# Sampling.net
KiCad netlist of a schematic drawn in Altium Designer
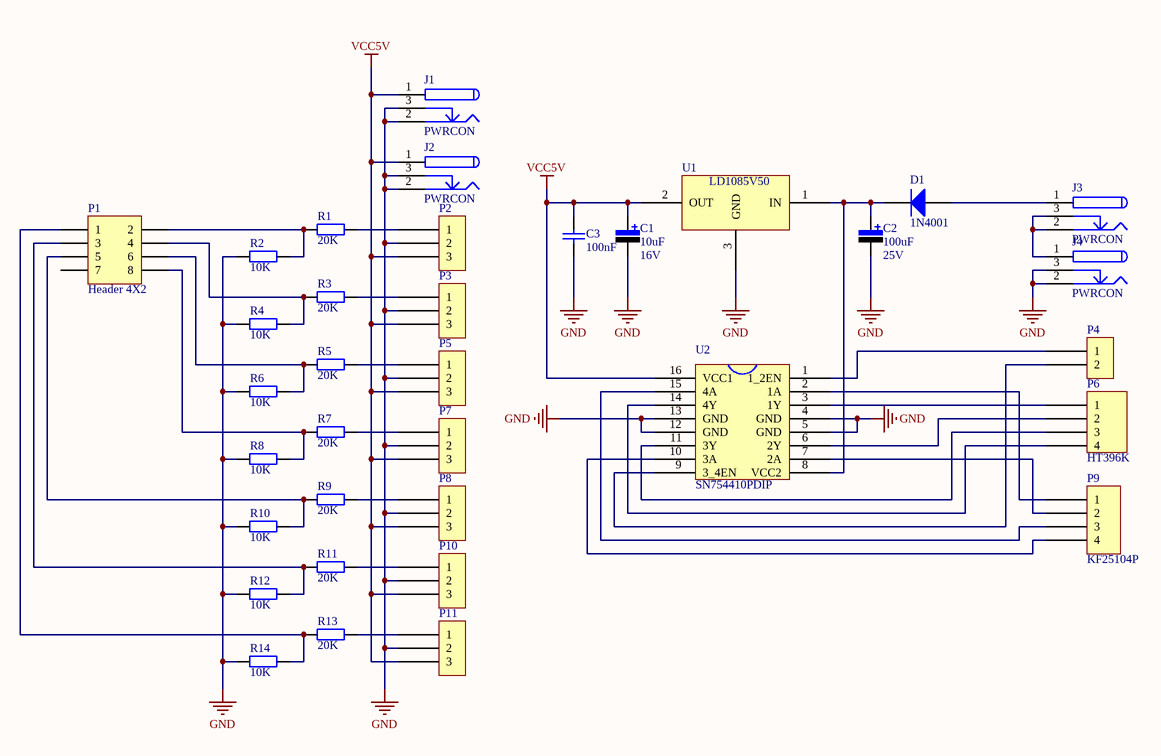
[diagram p0: Sampling.SchDoc]

(export (version "E")
  (design (tool "Eeschema 10.0.6"))
  (components
    (comp (ref "C1")
      (value "10uF")
      (footprint "C-RB-S4")
      (description "极性电解电容")
      (fields
        (field (name "VOL") "16V")
        (field (name "Comment") "Cap Pol")
        (field (name "PUBLISHER") "Altium Limited")
      )
      (libsource (lib "fszhang") (part "Cap Pol"))
    )
    (comp (ref "C2")
      (value "100uF")
      (footprint "C-RB-S6")
      (description "极性电解电容")
      (fields
        (field (name "VOL") "25V")
        (field (name "Comment") "Cap Pol")
        (field (name "PUBLISHER") "Altium Limited")
      )
      (libsource (lib "fszhang") (part "Cap Pol"))
    )
    (comp (ref "C3")
      (value "100nF")
      (footprint "C-RAD-0805")
      (description "无极性电容")
      (fields (field (name "Comment") "Cap") (field (name "PUBLISHER") "Altium Limited"))
      (libsource (lib "fszhang") (part "Cap"))
    )
    (comp (ref "D1")
      (value "Diode")
      (footprint "DIODE-SMA")
      (description "二极管")
      (fields (field (name "TYPE") "1N4001") (field (name "PUBLISHER") "Altium Limited"))
      (libsource (lib "fszhang") (part "Diode"))
    )
    (comp (ref "J1")
      (value "PWRCON")
      (footprint "DC-005")
      (description "直流电源端子")
      (fields (field (name "PUBLISHER") "Altium Limited"))
      (libsource (lib "fszhang") (part "PWRCON"))
    )
    (comp (ref "J2")
      (value "PWRCON")
      (footprint "DC-005")
      (description "直流电源端子")
      (fields (field (name "PUBLISHER") "Altium Limited"))
      (libsource (lib "fszhang") (part "PWRCON"))
    )
    (comp (ref "J3")
      (value "PWRCON")
      (footprint "DC-005")
      (description "直流电源端子")
      (fields (field (name "PUBLISHER") "Altium Limited"))
      (libsource (lib "fszhang") (part "PWRCON"))
    )
    (comp (ref "J4")
      (value "PWRCON")
      (footprint "DC-005")
      (description "直流电源端子")
      (fields (field (name "PUBLISHER") "Altium Limited"))
      (libsource (lib "fszhang") (part "PWRCON"))
    )
    (comp (ref "P1")
      (value "Header 4X2")
      (footprint "HDR2X4")
      (description "Header, 4-Pin, Dual row")
      (fields (field (name "PUBLISHER") "Altium Limited"))
      (libsource (lib "Miscellaneous Connectors") (part "Header 4X2"))
    )
    (comp (ref "P2") (value "KF25103P") (footprint "KF25103P") (libsource (lib "fszhang") (part "KF25103P")))
    (comp (ref "P3") (value "KF25103P") (footprint "KF25103P") (libsource (lib "fszhang") (part "KF25103P")))
    (comp (ref "P4") (value "KF25102P") (footprint "KF25102P") (libsource (lib "fszhang") (part "KF25102P")))
    (comp (ref "P5") (value "KF25103P") (footprint "KF25103P") (libsource (lib "fszhang") (part "KF25103P")))
    (comp (ref "P6") (value "HT396K") (footprint "HT396K") (libsource (lib "fszhang") (part "HT396K")))
    (comp (ref "P7") (value "KF25103P") (footprint "KF25103P") (libsource (lib "fszhang") (part "KF25103P")))
    (comp (ref "P8") (value "KF25103P") (footprint "KF25103P") (libsource (lib "fszhang") (part "KF25103P")))
    (comp (ref "P9") (value "KF25104P") (footprint "KF25104P") (libsource (lib "fszhang") (part "KF25104P")))
    (comp (ref "P10") (value "KF25103P") (footprint "KF25103P") (libsource (lib "fszhang") (part "KF25103P")))
    (comp (ref "P11") (value "KF25103P") (footprint "KF25103P") (libsource (lib "fszhang") (part "KF25103P")))
    (comp (ref "R1")
      (value "20K")
      (footprint "0805-1")
      (description "贴片电阻")
      (fields (field (name "Comment") "Res1") (field (name "PUBLISHER") "Altium Limited"))
      (libsource (lib "fszhang") (part "Res1"))
    )
    (comp (ref "R2")
      (value "10K")
      (footprint "0805-1")
      (description "贴片电阻")
      (fields (field (name "Comment") "Res1") (field (name "PUBLISHER") "Altium Limited"))
      (libsource (lib "fszhang") (part "Res1"))
    )
    (comp (ref "R3")
      (value "20K")
      (footprint "0805-1")
      (description "贴片电阻")
      (fields (field (name "Comment") "Res1") (field (name "PUBLISHER") "Altium Limited"))
      (libsource (lib "fszhang") (part "Res1"))
    )
    (comp (ref "R4")
      (value "10K")
      (footprint "0805-1")
      (description "贴片电阻")
      (fields (field (name "Comment") "Res1") (field (name "PUBLISHER") "Altium Limited"))
      (libsource (lib "fszhang") (part "Res1"))
    )
    (comp (ref "R5")
      (value "20K")
      (footprint "0805-1")
      (description "贴片电阻")
      (fields (field (name "Comment") "Res1") (field (name "PUBLISHER") "Altium Limited"))
      (libsource (lib "fszhang") (part "Res1"))
    )
    (comp (ref "R6")
      (value "10K")
      (footprint "0805-1")
      (description "贴片电阻")
      (fields (field (name "Comment") "Res1") (field (name "PUBLISHER") "Altium Limited"))
      (libsource (lib "fszhang") (part "Res1"))
    )
    (comp (ref "R7")
      (value "20K")
      (footprint "0805-1")
      (description "贴片电阻")
      (fields (field (name "Comment") "Res1") (field (name "PUBLISHER") "Altium Limited"))
      (libsource (lib "fszhang") (part "Res1"))
    )
    (comp (ref "R8")
      (value "10K")
      (footprint "0805-1")
      (description "贴片电阻")
      (fields (field (name "Comment") "Res1") (field (name "PUBLISHER") "Altium Limited"))
      (libsource (lib "fszhang") (part "Res1"))
    )
    (comp (ref "R9")
      (value "20K")
      (footprint "0805-1")
      (description "贴片电阻")
      (fields (field (name "Comment") "Res1") (field (name "PUBLISHER") "Altium Limited"))
      (libsource (lib "fszhang") (part "Res1"))
    )
    (comp (ref "R10")
      (value "10K")
      (footprint "0805-1")
      (description "贴片电阻")
      (fields (field (name "Comment") "Res1") (field (name "PUBLISHER") "Altium Limited"))
      (libsource (lib "fszhang") (part "Res1"))
    )
    (comp (ref "R11")
      (value "20K")
      (footprint "0805-1")
      (description "贴片电阻")
      (fields (field (name "Comment") "Res1") (field (name "PUBLISHER") "Altium Limited"))
      (libsource (lib "fszhang") (part "Res1"))
    )
    (comp (ref "R12")
      (value "10K")
      (footprint "0805-1")
      (description "贴片电阻")
      (fields (field (name "Comment") "Res1") (field (name "PUBLISHER") "Altium Limited"))
      (libsource (lib "fszhang") (part "Res1"))
    )
    (comp (ref "R13")
      (value "20K")
      (footprint "0805-1")
      (description "贴片电阻")
      (fields (field (name "Comment") "Res1") (field (name "PUBLISHER") "Altium Limited"))
      (libsource (lib "fszhang") (part "Res1"))
    )
    (comp (ref "R14")
      (value "10K")
      (footprint "0805-1")
      (description "贴片电阻")
      (fields (field (name "Comment") "Res1") (field (name "PUBLISHER") "Altium Limited"))
      (libsource (lib "fszhang") (part "Res1"))
    )
    (comp (ref "U1")
      (value "LD1085V50")
      (footprint "TO-220-AB")
      (libsource (lib "fszhang") (part "LD1085V50"))
    )
    (comp (ref "U2")
      (value "SN754410PDIP")
      (footprint "DIP-16")
      (libsource (lib "fszhang") (part "SN754410PDIP"))
    )
  )
  (nets
    (net (code "1") (name "GND") (class "Default")
      (node (ref "C1") (pin "2") (pinfunction "2_2") (pintype "passive"))
      (node (ref "C2") (pin "2") (pinfunction "2_2") (pintype "passive"))
      (node (ref "C3") (pin "1") (pinfunction "1_1") (pintype "passive"))
      (node (ref "J1") (pin "2") (pinfunction "2_2") (pintype "power_in"))
      (node (ref "J1") (pin "3") (pinfunction "3_3") (pintype "power_in"))
      (node (ref "J2") (pin "2") (pinfunction "2_2") (pintype "power_in"))
      (node (ref "J2") (pin "3") (pinfunction "3_3") (pintype "power_in"))
      (node (ref "J4") (pin "2") (pinfunction "2_2") (pintype "power_in"))
      (node (ref "J4") (pin "3") (pinfunction "3_3") (pintype "power_in"))
      (node (ref "P10") (pin "2") (pinfunction "2_2") (pintype "passive"))
      (node (ref "P11") (pin "2") (pinfunction "2_2") (pintype "passive"))
      (node (ref "P2") (pin "2") (pinfunction "2_2") (pintype "passive"))
      (node (ref "P3") (pin "2") (pinfunction "2_2") (pintype "passive"))
      (node (ref "P5") (pin "2") (pinfunction "2_2") (pintype "passive"))
      (node (ref "P7") (pin "2") (pinfunction "2_2") (pintype "passive"))
      (node (ref "P8") (pin "2") (pinfunction "2_2") (pintype "passive"))
      (node (ref "R10") (pin "1") (pinfunction "1_1") (pintype "passive"))
      (node (ref "R12") (pin "1") (pinfunction "1_1") (pintype "passive"))
      (node (ref "R14") (pin "1") (pinfunction "1_1") (pintype "passive"))
      (node (ref "R2") (pin "1") (pinfunction "1_1") (pintype "passive"))
      (node (ref "R4") (pin "1") (pinfunction "1_1") (pintype "passive"))
      (node (ref "R6") (pin "1") (pinfunction "1_1") (pintype "passive"))
      (node (ref "R8") (pin "1") (pinfunction "1_1") (pintype "passive"))
      (node (ref "U1") (pin "3") (pinfunction "GND_3") (pintype "passive"))
      (node (ref "U2") (pin "12") (pinfunction "GND_12") (pintype "passive"))
      (node (ref "U2") (pin "13") (pinfunction "GND_13") (pintype "passive"))
      (node (ref "U2") (pin "4") (pinfunction "GND_4") (pintype "passive"))
      (node (ref "U2") (pin "5") (pinfunction "GND_5") (pintype "passive"))
    )
    (net (code "2") (name "Net-(D1-A)") (class "Default")
      (node (ref "D1") (pin "1") (pinfunction "A_1") (pintype "passive"))
      (node (ref "J3") (pin "1") (pinfunction "1_1") (pintype "power_in"))
    )
    (net (code "3") (name "Net-(D1-K)") (class "Default")
      (node (ref "C2") (pin "1") (pinfunction "1_1") (pintype "passive"))
      (node (ref "D1") (pin "2") (pinfunction "K_2") (pintype "passive"))
      (node (ref "U1") (pin "1") (pinfunction "IN_1") (pintype "passive"))
      (node (ref "U2") (pin "8") (pinfunction "VCC2_8") (pintype "passive"))
    )
    (net (code "4") (name "Net-(J3-Pad2)") (class "Default")
      (node (ref "J3") (pin "2") (pinfunction "2_2") (pintype "power_in"))
      (node (ref "J3") (pin "3") (pinfunction "3_3") (pintype "power_in"))
      (node (ref "J4") (pin "1") (pinfunction "1_1") (pintype "power_in"))
    )
    (net (code "5") (name "Net-(P1-Pad1)") (class "Default")
      (node (ref "P1") (pin "1") (pinfunction "1_1") (pintype "passive"))
      (node (ref "R13") (pin "1") (pinfunction "1_1") (pintype "passive"))
      (node (ref "R14") (pin "2") (pinfunction "2_2") (pintype "passive"))
    )
    (net (code "6") (name "Net-(P1-Pad2)") (class "Default")
      (node (ref "P1") (pin "2") (pinfunction "2_2") (pintype "passive"))
      (node (ref "R1") (pin "1") (pinfunction "1_1") (pintype "passive"))
      (node (ref "R2") (pin "2") (pinfunction "2_2") (pintype "passive"))
    )
    (net (code "7") (name "Net-(P1-Pad3)") (class "Default")
      (node (ref "P1") (pin "3") (pinfunction "3_3") (pintype "passive"))
      (node (ref "R11") (pin "1") (pinfunction "1_1") (pintype "passive"))
      (node (ref "R12") (pin "2") (pinfunction "2_2") (pintype "passive"))
    )
    (net (code "8") (name "Net-(P1-Pad4)") (class "Default")
      (node (ref "P1") (pin "4") (pinfunction "4_4") (pintype "passive"))
      (node (ref "R3") (pin "1") (pinfunction "1_1") (pintype "passive"))
      (node (ref "R4") (pin "2") (pinfunction "2_2") (pintype "passive"))
    )
    (net (code "9") (name "Net-(P1-Pad5)") (class "Default")
      (node (ref "P1") (pin "5") (pinfunction "5_5") (pintype "passive"))
      (node (ref "R10") (pin "2") (pinfunction "2_2") (pintype "passive"))
      (node (ref "R9") (pin "1") (pinfunction "1_1") (pintype "passive"))
    )
    (net (code "10") (name "Net-(P1-Pad6)") (class "Default")
      (node (ref "P1") (pin "6") (pinfunction "6_6") (pintype "passive"))
      (node (ref "R5") (pin "1") (pinfunction "1_1") (pintype "passive"))
      (node (ref "R6") (pin "2") (pinfunction "2_2") (pintype "passive"))
    )
    (net (code "11") (name "Net-(P1-Pad8)") (class "Default")
      (node (ref "P1") (pin "8") (pinfunction "8_8") (pintype "passive"))
      (node (ref "R7") (pin "1") (pinfunction "1_1") (pintype "passive"))
      (node (ref "R8") (pin "2") (pinfunction "2_2") (pintype "passive"))
    )
    (net (code "12") (name "Net-(P2-Pad1)") (class "Default")
      (node (ref "P2") (pin "1") (pinfunction "1_1") (pintype "passive"))
      (node (ref "R1") (pin "2") (pinfunction "2_2") (pintype "passive"))
    )
    (net (code "13") (name "Net-(P3-Pad1)") (class "Default")
      (node (ref "P3") (pin "1") (pinfunction "1_1") (pintype "passive"))
      (node (ref "R3") (pin "2") (pinfunction "2_2") (pintype "passive"))
    )
    (net (code "14") (name "Net-(P5-Pad1)") (class "Default")
      (node (ref "P5") (pin "1") (pinfunction "1_1") (pintype "passive"))
      (node (ref "R5") (pin "2") (pinfunction "2_2") (pintype "passive"))
    )
    (net (code "15") (name "Net-(P7-Pad1)") (class "Default")
      (node (ref "P7") (pin "1") (pinfunction "1_1") (pintype "passive"))
      (node (ref "R7") (pin "2") (pinfunction "2_2") (pintype "passive"))
    )
    (net (code "16") (name "Net-(P8-Pad1)") (class "Default")
      (node (ref "P8") (pin "1") (pinfunction "1_1") (pintype "passive"))
      (node (ref "R9") (pin "2") (pinfunction "2_2") (pintype "passive"))
    )
    (net (code "17") (name "Net-(P10-Pad1)") (class "Default")
      (node (ref "P10") (pin "1") (pinfunction "1_1") (pintype "passive"))
      (node (ref "R11") (pin "2") (pinfunction "2_2") (pintype "passive"))
    )
    (net (code "18") (name "Net-(P11-Pad1)") (class "Default")
      (node (ref "P11") (pin "1") (pinfunction "1_1") (pintype "passive"))
      (node (ref "R13") (pin "2") (pinfunction "2_2") (pintype "passive"))
    )
    (net (code "19") (name "Net-(U2-1A)") (class "Default")
      (node (ref "P9") (pin "1") (pinfunction "1_1") (pintype "passive"))
      (node (ref "U2") (pin "2") (pinfunction "1A_2") (pintype "passive"))
    )
    (net (code "20") (name "Net-(U2-1Y)") (class "Default")
      (node (ref "P6") (pin "1") (pinfunction "1_1") (pintype "passive"))
      (node (ref "U2") (pin "3") (pinfunction "1Y_3") (pintype "passive"))
    )
    (net (code "21") (name "Net-(U2-1_2EN)") (class "Default")
      (node (ref "P4") (pin "1") (pinfunction "1_1") (pintype "passive"))
      (node (ref "U2") (pin "1") (pinfunction "1_2EN_1") (pintype "passive"))
    )
    (net (code "22") (name "Net-(U2-2A)") (class "Default")
      (node (ref "P9") (pin "2") (pinfunction "2_2") (pintype "passive"))
      (node (ref "U2") (pin "7") (pinfunction "2A_7") (pintype "passive"))
    )
    (net (code "23") (name "Net-(U2-2Y)") (class "Default")
      (node (ref "P6") (pin "2") (pinfunction "2_2") (pintype "passive"))
      (node (ref "U2") (pin "6") (pinfunction "2Y_6") (pintype "passive"))
    )
    (net (code "24") (name "Net-(U2-3A)") (class "Default")
      (node (ref "P9") (pin "4") (pinfunction "4_4") (pintype "passive"))
      (node (ref "U2") (pin "10") (pinfunction "3A_10") (pintype "passive"))
    )
    (net (code "25") (name "Net-(U2-3Y)") (class "Default")
      (node (ref "P6") (pin "3") (pinfunction "3_3") (pintype "passive"))
      (node (ref "U2") (pin "11") (pinfunction "3Y_11") (pintype "passive"))
    )
    (net (code "26") (name "Net-(U2-3_4EN)") (class "Default")
      (node (ref "P4") (pin "2") (pinfunction "2_2") (pintype "passive"))
      (node (ref "U2") (pin "9") (pinfunction "3_4EN_9") (pintype "passive"))
    )
    (net (code "27") (name "Net-(U2-4A)") (class "Default")
      (node (ref "P9") (pin "3") (pinfunction "3_3") (pintype "passive"))
      (node (ref "U2") (pin "15") (pinfunction "4A_15") (pintype "passive"))
    )
    (net (code "28") (name "Net-(U2-4Y)") (class "Default")
      (node (ref "P6") (pin "4") (pinfunction "4_4") (pintype "passive"))
      (node (ref "U2") (pin "14") (pinfunction "4Y_14") (pintype "passive"))
    )
    (net (code "29") (name "VCC5V") (class "Default")
      (node (ref "C1") (pin "1") (pinfunction "1_1") (pintype "passive"))
      (node (ref "C3") (pin "2") (pinfunction "2_2") (pintype "passive"))
      (node (ref "J1") (pin "1") (pinfunction "1_1") (pintype "power_in"))
      (node (ref "J2") (pin "1") (pinfunction "1_1") (pintype "power_in"))
      (node (ref "P10") (pin "3") (pinfunction "3_3") (pintype "passive"))
      (node (ref "P11") (pin "3") (pinfunction "3_3") (pintype "passive"))
      (node (ref "P2") (pin "3") (pinfunction "3_3") (pintype "passive"))
      (node (ref "P3") (pin "3") (pinfunction "3_3") (pintype "passive"))
      (node (ref "P5") (pin "3") (pinfunction "3_3") (pintype "passive"))
      (node (ref "P7") (pin "3") (pinfunction "3_3") (pintype "passive"))
      (node (ref "P8") (pin "3") (pinfunction "3_3") (pintype "passive"))
      (node (ref "U1") (pin "2") (pinfunction "OUT_2") (pintype "passive"))
      (node (ref "U2") (pin "16") (pinfunction "VCC1_16") (pintype "passive"))
    )
    (net (code "30") (name "unconnected-(P1-Pad7)") (class "Default")
      (node (ref "P1") (pin "7") (pinfunction "7_7") (pintype "passive"))
    )
  )
)
